# Solar_revb.net
KiCad netlist of a schematic drawn in EAGLE
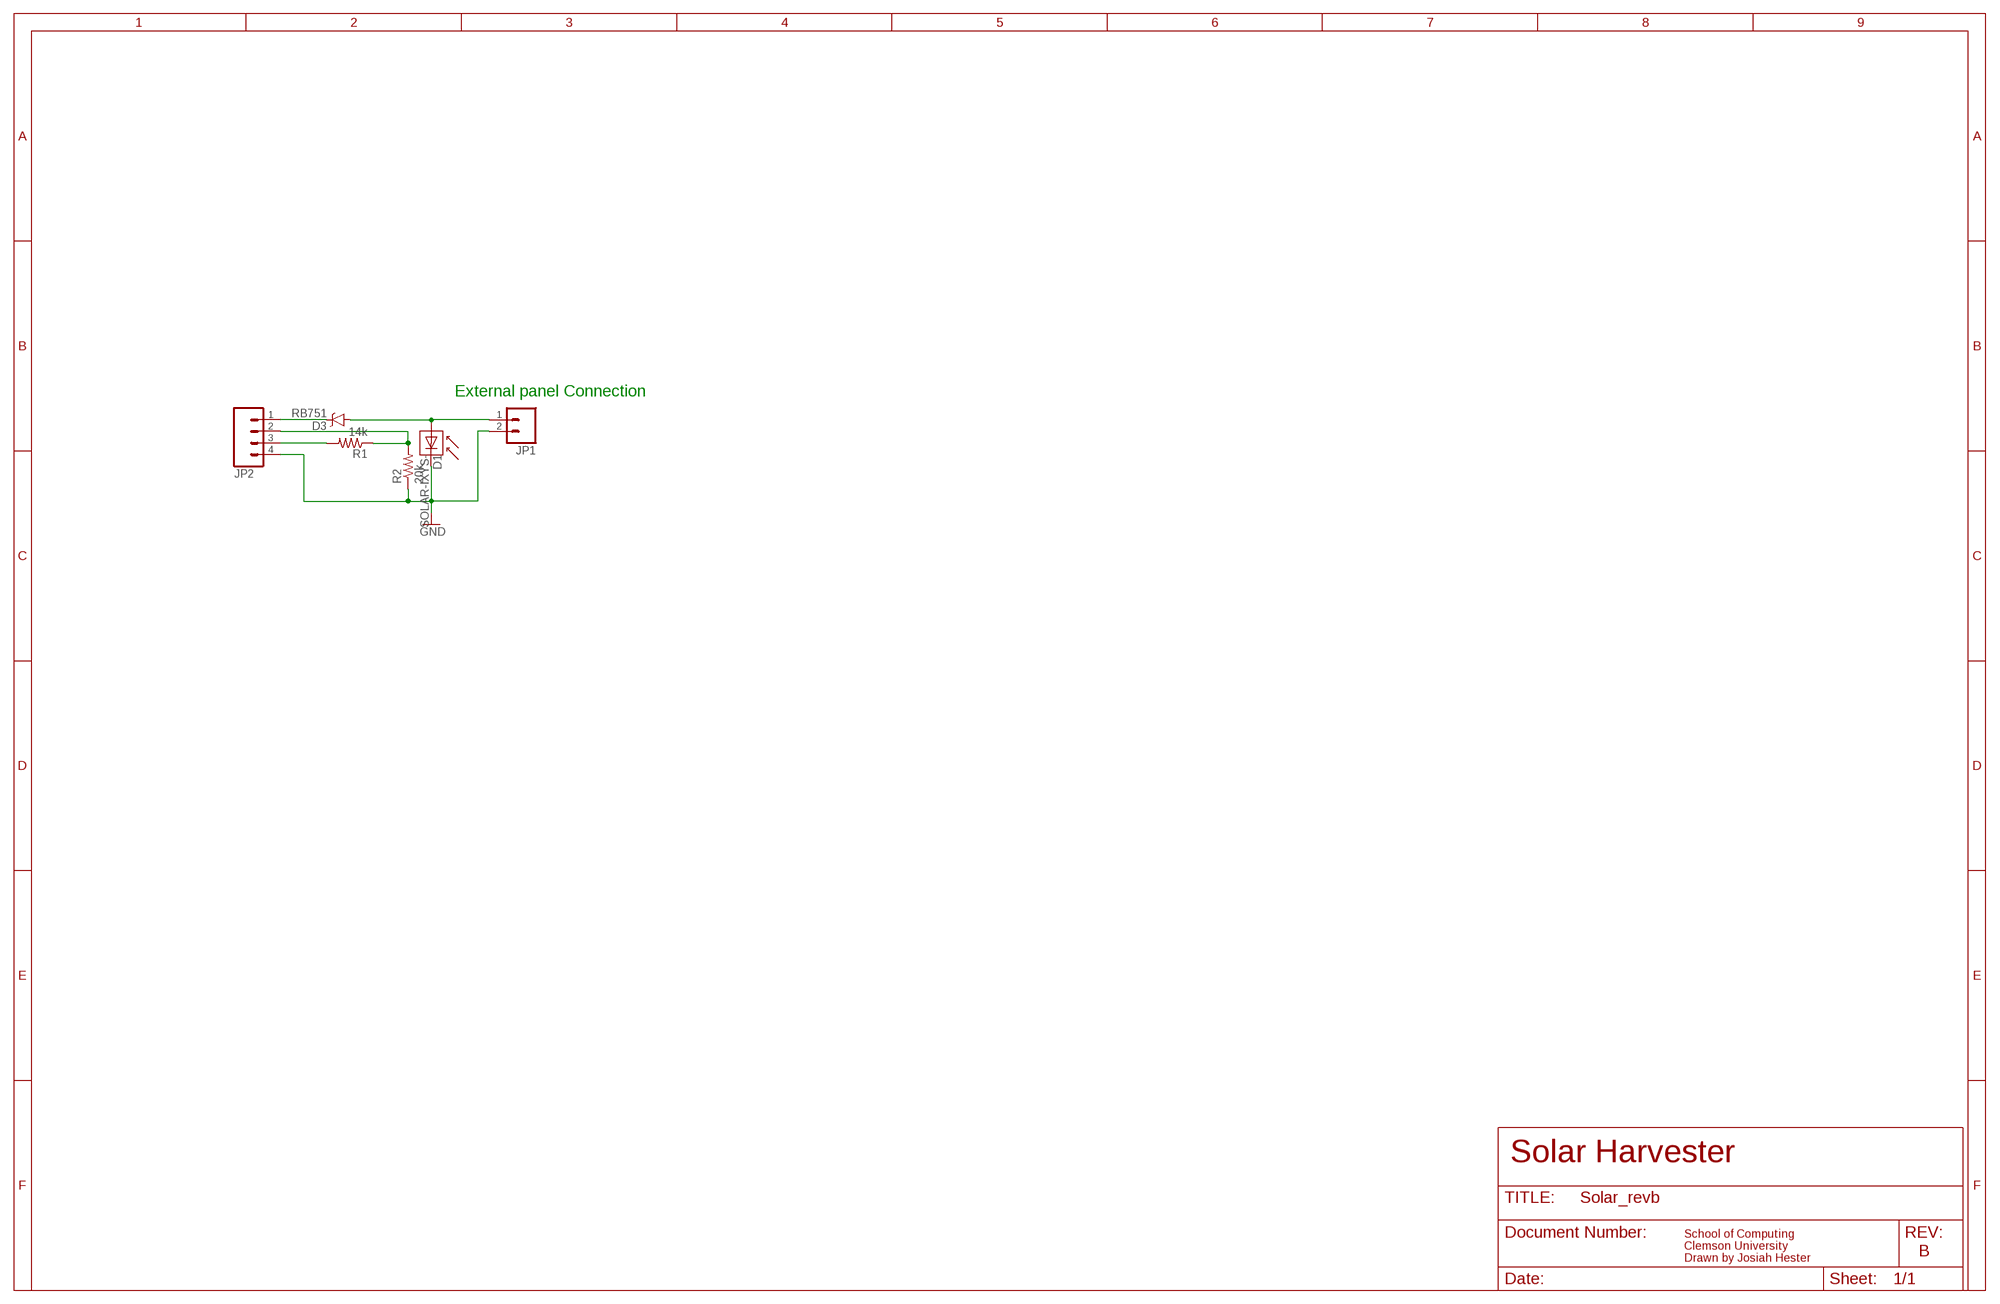
[diagram p0: schematic, sheet 1]

(export (version "E")
  (design (tool "Eeschema 10.0.6"))
  (components
    (comp (ref "D1")
      (value "SOLAR-IXYS-")
      (footprint "eagle-import:SOLARBIT-12X1")
      (libsource (lib "eagle-import") (part "SOLAR-IXYS-"))
    )
    (comp (ref "D3")
      (value "RB751")
      (footprint "eagle-import:SOD-523")
      (fields (field (name "MPN") "BAS40-02V-V-G-08"))
      (libsource (lib "eagle-import") (part "DIODE-SCHOTTKY-RB751"))
    )
    (comp (ref "JP1")
      (value "M02LOCK")
      (footprint "eagle-import:1X02_LOCK")
      (libsource (lib "eagle-import") (part "M02LOCK"))
    )
    (comp (ref "JP2")
      (value "M041.27MM")
      (footprint "eagle-import:1X04-1.27MM")
      (fields (field (name "MPN") "GRPB041VWVN-RC"))
      (libsource (lib "eagle-import") (part "M041.27MM"))
    )
    (comp (ref "R1")
      (value "14k")
      (footprint "eagle-import:0603")
      (fields (field (name "MPN") "CRCW060314K0FKEA"))
      (libsource (lib "eagle-import") (part "R-EU0603"))
    )
    (comp (ref "R2")
      (value "20k")
      (footprint "eagle-import:0603")
      (fields (field (name "MPN") "CRCW060320K0FKEA"))
      (libsource (lib "eagle-import") (part "R-EU0603"))
    )
  )
  (nets
    (net (code "1") (name "GND") (class "Default")
      (node (ref "D1") (pin "-") (pinfunction "C_-") (pintype "passive"))
      (node (ref "JP1") (pin "2") (pinfunction "2_2") (pintype "passive"))
      (node (ref "JP2") (pin "4") (pinfunction "4_4") (pintype "passive"))
      (node (ref "R2") (pin "1") (pinfunction "1_1") (pintype "passive"))
    )
    (net (code "2") (name "Net-(D1-A)") (class "Default")
      (node (ref "D1") (pin "+") (pinfunction "A_+") (pintype "passive"))
      (node (ref "D3") (pin "A") (pinfunction "A_A") (pintype "passive"))
      (node (ref "JP1") (pin "1") (pinfunction "1_1") (pintype "passive"))
    )
    (net (code "3") (name "Net-(D3-PadC)") (class "Default")
      (node (ref "D3") (pin "C") (pinfunction "C_C") (pintype "passive"))
      (node (ref "JP2") (pin "1") (pinfunction "1_1") (pintype "passive"))
    )
    (net (code "4") (name "Net-(JP2-Pad2)") (class "Default")
      (node (ref "JP2") (pin "2") (pinfunction "2_2") (pintype "passive"))
      (node (ref "R1") (pin "1") (pinfunction "1_1") (pintype "passive"))
      (node (ref "R2") (pin "2") (pinfunction "2_2") (pintype "passive"))
    )
    (net (code "5") (name "Net-(JP2-Pad3)") (class "Default")
      (node (ref "JP2") (pin "3") (pinfunction "3_3") (pintype "passive"))
      (node (ref "R1") (pin "2") (pinfunction "2_2") (pintype "passive"))
    )
  )
)
